# Prozessor.net
KiCad netlist of a schematic drawn in Altium Designer
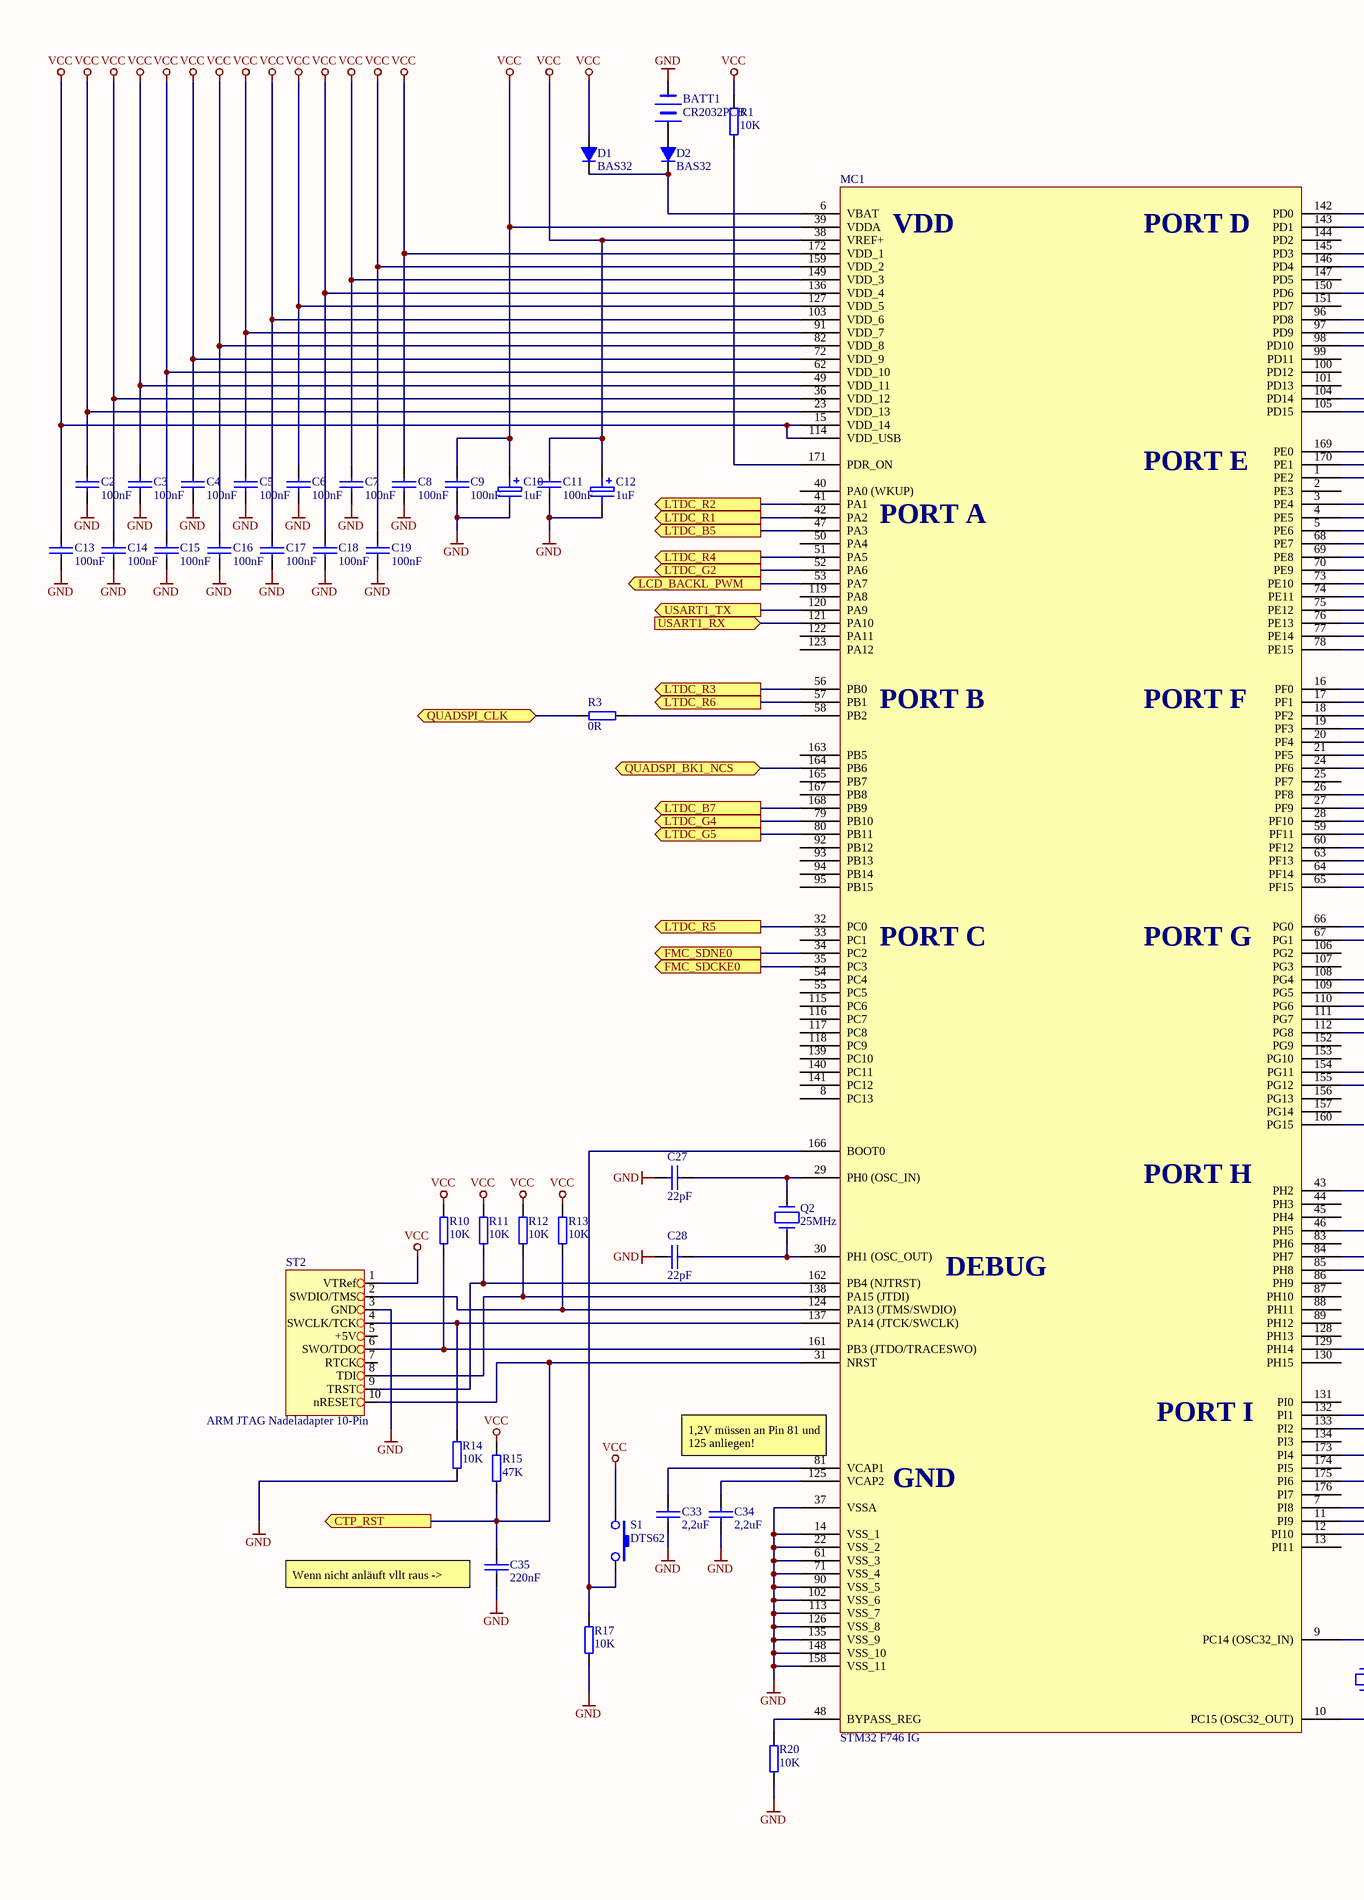
[diagram p0: Prozessor.SchDoc, left]
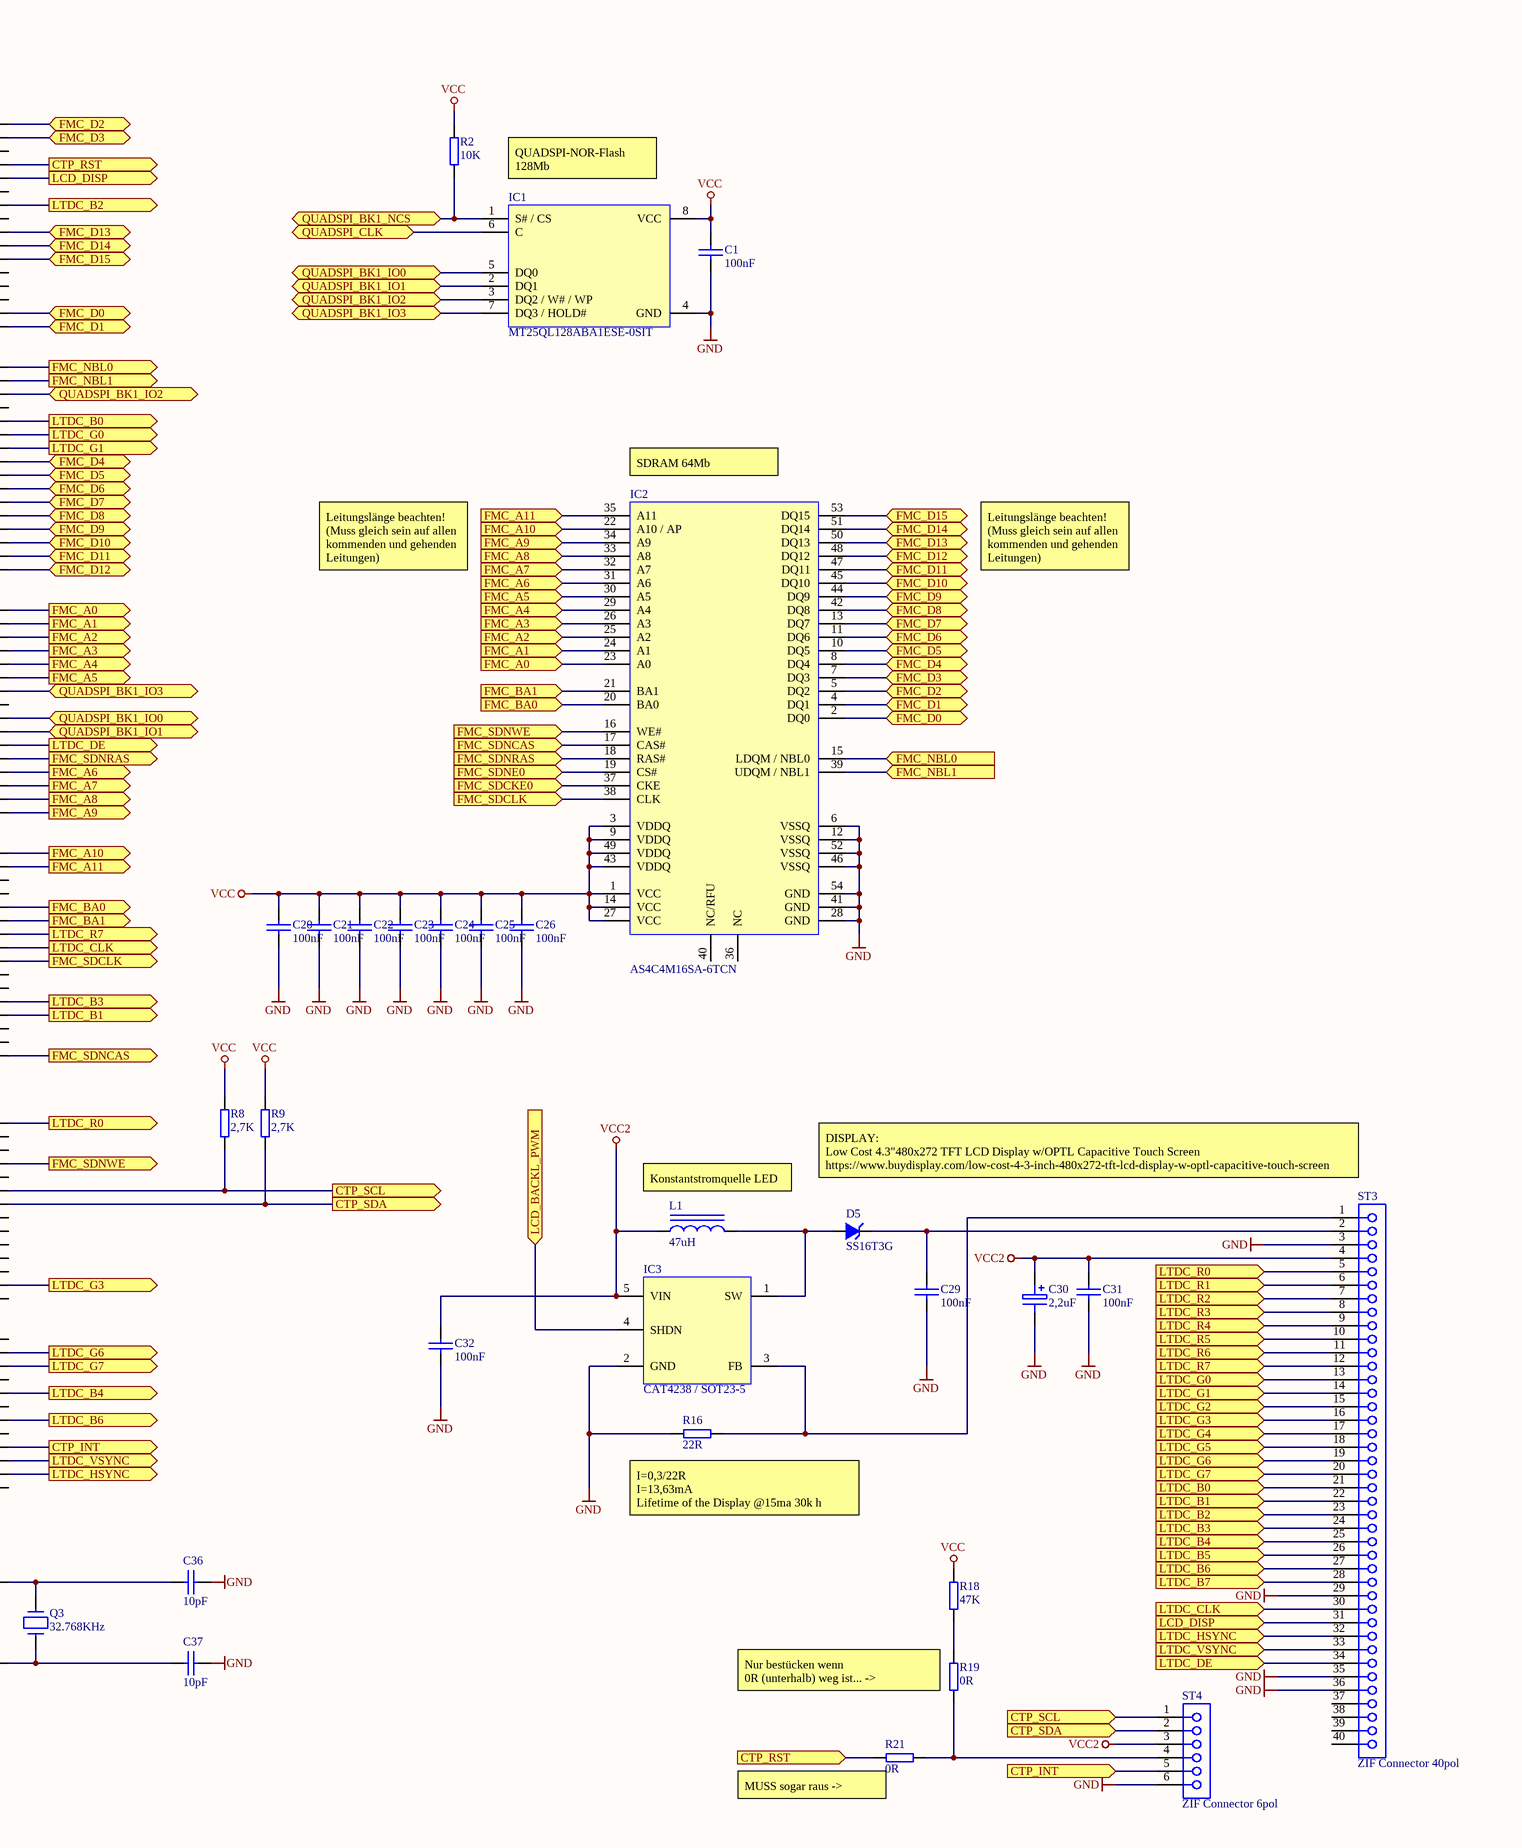
[diagram p1: Prozessor.SchDoc, right]

(export (version "E")
  (design (tool "Eeschema 10.0.6"))
  (components
    (comp (ref "BATT1")
      (value "CR2032PCB")
      (footprint "KnopfzellenhalterCR2032")
      (description "Knopfzellenhalter für Lithium-Batterie CR2032")
      (libsource (lib "Batterien") (part "CR2032 / HALTER"))
    )
    (comp (ref "C1")
      (value "100nF")
      (footprint "C0603")
      (description "100nF 0603 SMD-Keramik X7R 10% 50V")
      (libsource (lib "Kondensatoren") (part "0603 / 100nF"))
    )
    (comp (ref "C2")
      (value "100nF")
      (footprint "C0603")
      (description "100nF 0603 SMD-Keramik X7R 10% 50V")
      (libsource (lib "Kondensatoren") (part "0603 / 100nF"))
    )
    (comp (ref "C3")
      (value "100nF")
      (footprint "C0603")
      (description "100nF 0603 SMD-Keramik X7R 10% 50V")
      (libsource (lib "Kondensatoren") (part "0603 / 100nF"))
    )
    (comp (ref "C4")
      (value "100nF")
      (footprint "C0603")
      (description "100nF 0603 SMD-Keramik X7R 10% 50V")
      (libsource (lib "Kondensatoren") (part "0603 / 100nF"))
    )
    (comp (ref "C5")
      (value "100nF")
      (footprint "C0603")
      (description "100nF 0603 SMD-Keramik X7R 10% 50V")
      (libsource (lib "Kondensatoren") (part "0603 / 100nF"))
    )
    (comp (ref "C6")
      (value "100nF")
      (footprint "C0603")
      (description "100nF 0603 SMD-Keramik X7R 10% 50V")
      (libsource (lib "Kondensatoren") (part "0603 / 100nF"))
    )
    (comp (ref "C7")
      (value "100nF")
      (footprint "C0603")
      (description "100nF 0603 SMD-Keramik X7R 10% 50V")
      (libsource (lib "Kondensatoren") (part "0603 / 100nF"))
    )
    (comp (ref "C8")
      (value "100nF")
      (footprint "C0603")
      (description "100nF 0603 SMD-Keramik X7R 10% 50V")
      (libsource (lib "Kondensatoren") (part "0603 / 100nF"))
    )
    (comp (ref "C9")
      (value "100nF")
      (footprint "C0603")
      (description "100nF 0603 SMD-Keramik X7R 10% 50V")
      (libsource (lib "Kondensatoren") (part "0603 / 100nF"))
    )
    (comp (ref "C10")
      (value "1uF")
      (footprint "Alu-Elko4x5")
      (description "SMD-Alu Elko 1uF / 50V")
      (libsource (lib "Kondensatoren") (part "1uF / 50V"))
    )
    (comp (ref "C11")
      (value "100nF")
      (footprint "C0603")
      (description "100nF 0603 SMD-Keramik X7R 10% 50V")
      (libsource (lib "Kondensatoren") (part "0603 / 100nF"))
    )
    (comp (ref "C12")
      (value "1uF")
      (footprint "Alu-Elko4x5")
      (description "SMD-Alu Elko 1uF / 50V")
      (libsource (lib "Kondensatoren") (part "1uF / 50V"))
    )
    (comp (ref "C13")
      (value "100nF")
      (footprint "C0603")
      (description "100nF 0603 SMD-Keramik X7R 10% 50V")
      (libsource (lib "Kondensatoren") (part "0603 / 100nF"))
    )
    (comp (ref "C14")
      (value "100nF")
      (footprint "C0603")
      (description "100nF 0603 SMD-Keramik X7R 10% 50V")
      (libsource (lib "Kondensatoren") (part "0603 / 100nF"))
    )
    (comp (ref "C15")
      (value "100nF")
      (footprint "C0603")
      (description "100nF 0603 SMD-Keramik X7R 10% 50V")
      (libsource (lib "Kondensatoren") (part "0603 / 100nF"))
    )
    (comp (ref "C16")
      (value "100nF")
      (footprint "C0603")
      (description "100nF 0603 SMD-Keramik X7R 10% 50V")
      (libsource (lib "Kondensatoren") (part "0603 / 100nF"))
    )
    (comp (ref "C17")
      (value "100nF")
      (footprint "C0603")
      (description "100nF 0603 SMD-Keramik X7R 10% 50V")
      (libsource (lib "Kondensatoren") (part "0603 / 100nF"))
    )
    (comp (ref "C18")
      (value "100nF")
      (footprint "C0603")
      (description "100nF 0603 SMD-Keramik X7R 10% 50V")
      (libsource (lib "Kondensatoren") (part "0603 / 100nF"))
    )
    (comp (ref "C19")
      (value "100nF")
      (footprint "C0603")
      (description "100nF 0603 SMD-Keramik X7R 10% 50V")
      (libsource (lib "Kondensatoren") (part "0603 / 100nF"))
    )
    (comp (ref "C20")
      (value "100nF")
      (footprint "C0603")
      (description "100nF 0603 SMD-Keramik X7R 10% 50V")
      (libsource (lib "Kondensatoren") (part "0603 / 100nF"))
    )
    (comp (ref "C21")
      (value "100nF")
      (footprint "C0603")
      (description "100nF 0603 SMD-Keramik X7R 10% 50V")
      (libsource (lib "Kondensatoren") (part "0603 / 100nF"))
    )
    (comp (ref "C22")
      (value "100nF")
      (footprint "C0603")
      (description "100nF 0603 SMD-Keramik X7R 10% 50V")
      (libsource (lib "Kondensatoren") (part "0603 / 100nF"))
    )
    (comp (ref "C23")
      (value "100nF")
      (footprint "C0603")
      (description "100nF 0603 SMD-Keramik X7R 10% 50V")
      (libsource (lib "Kondensatoren") (part "0603 / 100nF"))
    )
    (comp (ref "C24")
      (value "100nF")
      (footprint "C0603")
      (description "100nF 0603 SMD-Keramik X7R 10% 50V")
      (libsource (lib "Kondensatoren") (part "0603 / 100nF"))
    )
    (comp (ref "C25")
      (value "100nF")
      (footprint "C0603")
      (description "100nF 0603 SMD-Keramik X7R 10% 50V")
      (libsource (lib "Kondensatoren") (part "0603 / 100nF"))
    )
    (comp (ref "C26")
      (value "100nF")
      (footprint "C0603")
      (description "100nF 0603 SMD-Keramik X7R 10% 50V")
      (libsource (lib "Kondensatoren") (part "0603 / 100nF"))
    )
    (comp (ref "C27")
      (value "22pF")
      (footprint "C0603")
      (description "22pF 0603 SMD-Keramik X7R 10% 50V")
      (libsource (lib "Kondensatoren") (part "0603 / 22pF"))
    )
    (comp (ref "C28")
      (value "22pF")
      (footprint "C0603")
      (description "22pF 0603 SMD-Keramik X7R 10% 50V")
      (libsource (lib "Kondensatoren") (part "0603 / 22pF"))
    )
    (comp (ref "C29")
      (value "100nF")
      (footprint "C0603")
      (description "100nF 0603 SMD-Keramik X7R 10% 50V")
      (libsource (lib "Kondensatoren") (part "0603 / 100nF"))
    )
    (comp (ref "C30")
      (value "2,2uF")
      (footprint "CB")
      (description "SMD-Tantal 2,2uF / 25V 20% B")
      (libsource (lib "Kondensatoren") (part "2,2uF / 25V"))
    )
    (comp (ref "C31")
      (value "100nF")
      (footprint "C0603")
      (description "100nF 0603 SMD-Keramik X7R 10% 50V")
      (libsource (lib "Kondensatoren") (part "0603 / 100nF"))
    )
    (comp (ref "C32")
      (value "100nF")
      (footprint "C0603")
      (description "100nF 0603 SMD-Keramik X7R 10% 50V")
      (libsource (lib "Kondensatoren") (part "0603 / 100nF"))
    )
    (comp (ref "C33")
      (value "2,2uF")
      (footprint "C1206")
      (description "2,2uF 1206 SMD-Keramik 10% 50V XR7")
      (libsource (lib "Kondensatoren") (part "1206 / 2,2uF"))
    )
    (comp (ref "C34")
      (value "2,2uF")
      (footprint "C1206")
      (description "2,2uF 1206 SMD-Keramik 10% 50V XR7")
      (libsource (lib "Kondensatoren") (part "1206 / 2,2uF"))
    )
    (comp (ref "C35")
      (value "220nF")
      (footprint "C0603")
      (description "220nF 0603 SMD-Keramik X7R 10% 50V")
      (libsource (lib "Kondensatoren") (part "0603 / 220nF"))
    )
    (comp (ref "C36")
      (value "10pF")
      (footprint "C0603")
      (description "10pF 0603 SMD-Keramik X7R 10% 50V")
      (libsource (lib "Kondensatoren") (part "0603 / 10pF"))
    )
    (comp (ref "C37")
      (value "10pF")
      (footprint "C0603")
      (description "10pF 0603 SMD-Keramik X7R 10% 50V")
      (libsource (lib "Kondensatoren") (part "0603 / 10pF"))
    )
    (comp (ref "D1")
      (value "BAS32")
      (footprint "Minimelf")
      (description "SMD Si-Diode 100V 0,2A Minimelf")
      (libsource (lib "Dioden") (part "BAS32 / MINIMELF"))
    )
    (comp (ref "D2")
      (value "BAS32")
      (footprint "Minimelf")
      (description "SMD Si-Diode 100V 0,2A Minimelf")
      (libsource (lib "Dioden") (part "BAS32 / MINIMELF"))
    )
    (comp (ref "D5")
      (value "SS16T3G")
      (footprint "DO214AC/SMA")
      (description "Schottky Diode 60V 1A")
      (libsource (lib "Dioden") (part "SS16T3G"))
    )
    (comp (ref "IC1")
      (value "MT25QL128ABA1ESE-0SIT")
      (footprint "SOP2-8-208 (SO8W)")
      (description "SPI-NOR-Flash 128Mb")
      (libsource (lib "Speicher") (part "MT25QL128ABA1ESE-0SIT / SO8W"))
    )
    (comp (ref "IC2")
      (value "AS4C4M16SA-6TCN")
      (footprint "TSSOP(2)54")
      (description "SDRAM 64Mb")
      (libsource (lib "Speicher") (part "AS4C4M16SA-6TCN / SO8W_1"))
    )
    (comp (ref "IC3")
      (value "CAT4238 / SOT23-5")
      (footprint "SOT23-5")
      (description "LED Driver, Boost, 10LED")
      (libsource (lib "Linear") (part "CAT4238 / SOT23-5"))
    )
    (comp (ref "L1")
      (value "47uH")
      (footprint "P8X9")
      (description "Tonneninduktivität stehend")
      (libsource (lib "Induktivitaeten") (part "47uH / P8X9"))
    )
    (comp (ref "MC1")
      (value "STM32 F746 IG")
      (footprint "QFP24x24-176-05")
      (description "LQFP 1176 24x24")
      (libsource (lib "Microcontroller") (part "STM32 F746 IG"))
    )
    (comp (ref "Q2")
      (value "25MHz")
      (footprint "HC49S4SMD")
      (description "SMD Schwingquarz 8MHz HC49S$SMD 30ppm")
      (libsource (lib "Quarze") (part "HC49 S / 8"))
    )
    (comp (ref "Q3")
      (value "32.768KHz")
      (footprint "SMD Uhrenquarz klein")
      (description "SMD Schwingquarz 32.768KHz 15ppm")
      (libsource (lib "Quarze") (part "ZM315-32.768"))
    )
    (comp (ref "R1")
      (value "10K")
      (footprint "R0603")
      (description "10K 0603 SMD-Kohleschicht 1% 0,1W")
      (libsource (lib "Widerstaende") (part "0603 / 10K"))
    )
    (comp (ref "R2")
      (value "10K")
      (footprint "R0603")
      (description "10K 0603 SMD-Kohleschicht 1% 0,1W")
      (libsource (lib "Widerstaende") (part "0603 / 10K"))
    )
    (comp (ref "R3")
      (value "0R")
      (footprint "R0603")
      (description "0R 0603 SMD-Kohleschicht 1% 0,1W")
      (libsource (lib "Widerstaende") (part "0603 / 0R"))
    )
    (comp (ref "R8")
      (value "2,7K")
      (footprint "R0603")
      (description "2,7K 0603 SMD-Kohleschicht 1% 0,1W")
      (libsource (lib "Widerstaende") (part "0603 / 2,7K"))
    )
    (comp (ref "R9")
      (value "2,7K")
      (footprint "R0603")
      (description "2,7K 0603 SMD-Kohleschicht 1% 0,1W")
      (libsource (lib "Widerstaende") (part "0603 / 2,7K"))
    )
    (comp (ref "R10")
      (value "10K")
      (footprint "R0603")
      (description "10K 0603 SMD-Kohleschicht 1% 0,1W")
      (libsource (lib "Widerstaende") (part "0603 / 10K"))
    )
    (comp (ref "R11")
      (value "10K")
      (footprint "R0603")
      (description "10K 0603 SMD-Kohleschicht 1% 0,1W")
      (libsource (lib "Widerstaende") (part "0603 / 10K"))
    )
    (comp (ref "R12")
      (value "10K")
      (footprint "R0603")
      (description "10K 0603 SMD-Kohleschicht 1% 0,1W")
      (libsource (lib "Widerstaende") (part "0603 / 10K"))
    )
    (comp (ref "R13")
      (value "10K")
      (footprint "R0603")
      (description "10K 0603 SMD-Kohleschicht 1% 0,1W")
      (libsource (lib "Widerstaende") (part "0603 / 10K"))
    )
    (comp (ref "R14")
      (value "10K")
      (footprint "R0603")
      (description "10K 0603 SMD-Kohleschicht 1% 0,1W")
      (libsource (lib "Widerstaende") (part "0603 / 10K"))
    )
    (comp (ref "R15")
      (value "47K")
      (footprint "R0603")
      (description "47K 0603 SMD-Kohleschicht 1% 0,1W")
      (libsource (lib "Widerstaende") (part "0603 / 47K"))
    )
    (comp (ref "R16")
      (value "22R")
      (footprint "R0603")
      (description "22R 0603 SMD-Kohleschicht 1% 0,1W")
      (libsource (lib "Widerstaende") (part "0603 / 22R"))
    )
    (comp (ref "R17")
      (value "10K")
      (footprint "R0603")
      (description "10K 0603 SMD-Kohleschicht 1% 0,1W")
      (libsource (lib "Widerstaende") (part "0603 / 10K"))
    )
    (comp (ref "R18")
      (value "47K")
      (footprint "R0603")
      (description "47K 0603 SMD-Kohleschicht 1% 0,1W")
      (libsource (lib "Widerstaende") (part "0603 / 47K"))
    )
    (comp (ref "R19")
      (value "0R")
      (footprint "R0603")
      (description "0R 0603 SMD-Kohleschicht 1% 0,1W")
      (libsource (lib "Widerstaende") (part "0603 / 0R"))
    )
    (comp (ref "R20")
      (value "10K")
      (footprint "R0603")
      (description "10K 0603 SMD-Kohleschicht 1% 0,1W")
      (libsource (lib "Widerstaende") (part "0603 / 10K"))
    )
    (comp (ref "R21")
      (value "0R")
      (footprint "R0603")
      (description "0R 0603 SMD-Kohleschicht 1% 0,1W")
      (libsource (lib "Widerstaende") (part "0603 / 0R"))
    )
    (comp (ref "S1")
      (value "DTS62")
      (footprint "DTS62")
      (description "Leiterplattentaster 6x6mm 1,6N")
      (libsource (lib "Schalter") (part "DTS62 / N"))
    )
    (comp (ref "ST2")
      (value "ARM JTAG Nadeladapter 10-Pin")
      (footprint "NADELADAPTER-10")
      (libsource (lib "Steckverbinder") (part "ARM JTAG Nadeladapter 10-Pin"))
    )
    (comp (ref "ST3")
      (value "ZIF Connector 40pol")
      (footprint "ZIF Connector 40pol")
      (description "ZIF Connector 40pol Top Contact")
      (libsource (lib "Steckverbinder") (part "ZIF Connector 40pol Top Contact"))
    )
    (comp (ref "ST4")
      (value "ZIF Connector 6pol")
      (footprint "ZIF Connector 6pol")
      (description "ZIF Connector 6pol Top Contact")
      (libsource (lib "Steckverbinder") (part "ZIF Connector 6pol Top Contact"))
    )
  )
  (nets
    (net (code "1") (name "/CTP_INT") (class "Default")
      (node (ref "MC1") (pin "7") (pinfunction "PI8_7") (pintype "passive"))
      (node (ref "ST4") (pin "5") (pinfunction "5_5") (pintype "passive"))
    )
    (net (code "2") (name "/CTP_RST") (class "Default")
      (node (ref "C35") (pin "2") (pintype "passive"))
      (node (ref "MC1") (pin "145") (pinfunction "PD3_145") (pintype "passive"))
      (node (ref "MC1") (pin "31") (pinfunction "NRST_31") (pintype "passive"))
      (node (ref "R15") (pin "1") (pintype "passive"))
      (node (ref "R21") (pin "1") (pintype "passive"))
      (node (ref "ST2") (pin "10") (pinfunction "nRESET_10") (pintype "passive"))
    )
    (net (code "3") (name "/CTP_SCL") (class "Default")
      (node (ref "MC1") (pin "84") (pinfunction "PH7_84") (pintype "passive"))
      (node (ref "R8") (pin "1") (pintype "passive"))
      (node (ref "ST4") (pin "1") (pinfunction "1_1") (pintype "passive"))
    )
    (net (code "4") (name "/CTP_SDA") (class "Default")
      (node (ref "MC1") (pin "85") (pinfunction "PH8_85") (pintype "passive"))
      (node (ref "R9") (pin "1") (pintype "passive"))
      (node (ref "ST4") (pin "2") (pinfunction "2_2") (pintype "passive"))
    )
    (net (code "5") (name "/FMC_A0") (class "Default")
      (node (ref "IC2") (pin "23") (pinfunction "A0_23") (pintype "passive"))
      (node (ref "MC1") (pin "16") (pinfunction "PF0_16") (pintype "passive"))
    )
    (net (code "6") (name "/FMC_A1") (class "Default")
      (node (ref "IC2") (pin "24") (pinfunction "A1_24") (pintype "passive"))
      (node (ref "MC1") (pin "17") (pinfunction "PF1_17") (pintype "passive"))
    )
    (net (code "7") (name "/FMC_A2") (class "Default")
      (node (ref "IC2") (pin "25") (pinfunction "A2_25") (pintype "passive"))
      (node (ref "MC1") (pin "18") (pinfunction "PF2_18") (pintype "passive"))
    )
    (net (code "8") (name "/FMC_A3") (class "Default")
      (node (ref "IC2") (pin "26") (pinfunction "A3_26") (pintype "passive"))
      (node (ref "MC1") (pin "19") (pinfunction "PF3_19") (pintype "passive"))
    )
    (net (code "9") (name "/FMC_A4") (class "Default")
      (node (ref "IC2") (pin "29") (pinfunction "A4_29") (pintype "passive"))
      (node (ref "MC1") (pin "20") (pinfunction "PF4_20") (pintype "passive"))
    )
    (net (code "10") (name "/FMC_A5") (class "Default")
      (node (ref "IC2") (pin "30") (pinfunction "A5_30") (pintype "passive"))
      (node (ref "MC1") (pin "21") (pinfunction "PF5_21") (pintype "passive"))
    )
    (net (code "11") (name "/FMC_A6") (class "Default")
      (node (ref "IC2") (pin "31") (pinfunction "A6_31") (pintype "passive"))
      (node (ref "MC1") (pin "60") (pinfunction "PF12_60") (pintype "passive"))
    )
    (net (code "12") (name "/FMC_A7") (class "Default")
      (node (ref "IC2") (pin "32") (pinfunction "A7_32") (pintype "passive"))
      (node (ref "MC1") (pin "63") (pinfunction "PF13_63") (pintype "passive"))
    )
    (net (code "13") (name "/FMC_A8") (class "Default")
      (node (ref "IC2") (pin "33") (pinfunction "A8_33") (pintype "passive"))
      (node (ref "MC1") (pin "64") (pinfunction "PF14_64") (pintype "passive"))
    )
    (net (code "14") (name "/FMC_A9") (class "Default")
      (node (ref "IC2") (pin "34") (pinfunction "A9_34") (pintype "passive"))
      (node (ref "MC1") (pin "65") (pinfunction "PF15_65") (pintype "passive"))
    )
    (net (code "15") (name "/FMC_A10") (class "Default")
      (node (ref "IC2") (pin "22") (pinfunction "A10_/_AP_22") (pintype "passive"))
      (node (ref "MC1") (pin "66") (pinfunction "PG0_66") (pintype "passive"))
    )
    (net (code "16") (name "/FMC_A11") (class "Default")
      (node (ref "IC2") (pin "35") (pinfunction "A11_35") (pintype "passive"))
      (node (ref "MC1") (pin "67") (pinfunction "PG1_67") (pintype "passive"))
    )
    (net (code "17") (name "/FMC_BA0") (class "Default")
      (node (ref "IC2") (pin "20") (pinfunction "BA0_20") (pintype "passive"))
      (node (ref "MC1") (pin "108") (pinfunction "PG4_108") (pintype "passive"))
    )
    (net (code "18") (name "/FMC_BA1") (class "Default")
      (node (ref "IC2") (pin "21") (pinfunction "BA1_21") (pintype "passive"))
      (node (ref "MC1") (pin "109") (pinfunction "PG5_109") (pintype "passive"))
    )
    (net (code "19") (name "/FMC_D0") (class "Default")
      (node (ref "IC2") (pin "2") (pinfunction "DQ0_2") (pintype "passive"))
      (node (ref "MC1") (pin "104") (pinfunction "PD14_104") (pintype "passive"))
    )
    (net (code "20") (name "/FMC_D1") (class "Default")
      (node (ref "IC2") (pin "4") (pinfunction "DQ1_4") (pintype "passive"))
      (node (ref "MC1") (pin "105") (pinfunction "PD15_105") (pintype "passive"))
    )
    (net (code "21") (name "/FMC_D2") (class "Default")
      (node (ref "IC2") (pin "5") (pinfunction "DQ2_5") (pintype "passive"))
      (node (ref "MC1") (pin "142") (pinfunction "PD0_142") (pintype "passive"))
    )
    (net (code "22") (name "/FMC_D3") (class "Default")
      (node (ref "IC2") (pin "7") (pinfunction "DQ3_7") (pintype "passive"))
      (node (ref "MC1") (pin "143") (pinfunction "PD1_143") (pintype "passive"))
    )
    (net (code "23") (name "/FMC_D4") (class "Default")
      (node (ref "IC2") (pin "8") (pinfunction "DQ4_8") (pintype "passive"))
      (node (ref "MC1") (pin "68") (pinfunction "PE7_68") (pintype "passive"))
    )
    (net (code "24") (name "/FMC_D5") (class "Default")
      (node (ref "IC2") (pin "10") (pinfunction "DQ5_10") (pintype "passive"))
      (node (ref "MC1") (pin "69") (pinfunction "PE8_69") (pintype "passive"))
    )
    (net (code "25") (name "/FMC_D6") (class "Default")
      (node (ref "IC2") (pin "11") (pinfunction "DQ6_11") (pintype "passive"))
      (node (ref "MC1") (pin "70") (pinfunction "PE9_70") (pintype "passive"))
    )
    (net (code "26") (name "/FMC_D7") (class "Default")
      (node (ref "IC2") (pin "13") (pinfunction "DQ7_13") (pintype "passive"))
      (node (ref "MC1") (pin "73") (pinfunction "PE10_73") (pintype "passive"))
    )
    (net (code "27") (name "/FMC_D8") (class "Default")
      (node (ref "IC2") (pin "42") (pinfunction "DQ8_42") (pintype "passive"))
      (node (ref "MC1") (pin "74") (pinfunction "PE11_74") (pintype "passive"))
    )
    (net (code "28") (name "/FMC_D9") (class "Default")
      (node (ref "IC2") (pin "44") (pinfunction "DQ9_44") (pintype "passive"))
      (node (ref "MC1") (pin "75") (pinfunction "PE12_75") (pintype "passive"))
    )
    (net (code "29") (name "/FMC_D10") (class "Default")
      (node (ref "IC2") (pin "45") (pinfunction "DQ10_45") (pintype "passive"))
      (node (ref "MC1") (pin "76") (pinfunction "PE13_76") (pintype "passive"))
    )
    (net (code "30") (name "/FMC_D11") (class "Default")
      (node (ref "IC2") (pin "47") (pinfunction "DQ11_47") (pintype "passive"))
      (node (ref "MC1") (pin "77") (pinfunction "PE14_77") (pintype "passive"))
    )
    (net (code "31") (name "/FMC_D12") (class "Default")
      (node (ref "IC2") (pin "48") (pinfunction "DQ12_48") (pintype "passive"))
      (node (ref "MC1") (pin "78") (pinfunction "PE15_78") (pintype "passive"))
    )
    (net (code "32") (name "/FMC_D13") (class "Default")
      (node (ref "IC2") (pin "50") (pinfunction "DQ13_50") (pintype "passive"))
      (node (ref "MC1") (pin "96") (pinfunction "PD8_96") (pintype "passive"))
    )
    (net (code "33") (name "/FMC_D14") (class "Default")
      (node (ref "IC2") (pin "51") (pinfunction "DQ14_51") (pintype "passive"))
      (node (ref "MC1") (pin "97") (pinfunction "PD9_97") (pintype "passive"))
    )
    (net (code "34") (name "/FMC_D15") (class "Default")
      (node (ref "IC2") (pin "53") (pinfunction "DQ15_53") (pintype "passive"))
      (node (ref "MC1") (pin "98") (pinfunction "PD10_98") (pintype "passive"))
    )
    (net (code "35") (name "/FMC_NBL0") (class "Default")
      (node (ref "IC2") (pin "15") (pinfunction "LDQM_/_NBL0_15") (pintype "passive"))
      (node (ref "MC1") (pin "169") (pinfunction "PE0_169") (pintype "passive"))
    )
    (net (code "36") (name "/FMC_NBL1") (class "Default")
      (node (ref "IC2") (pin "39") (pinfunction "UDQM_/_NBL1_39") (pintype "passive"))
      (node (ref "MC1") (pin "170") (pinfunction "PE1_170") (pintype "passive"))
    )
    (net (code "37") (name "/FMC_SDCKE0") (class "Default")
      (node (ref "IC2") (pin "37") (pinfunction "CKE_37") (pintype "passive"))
      (node (ref "MC1") (pin "35") (pinfunction "PC3_35") (pintype "passive"))
    )
    (net (code "38") (name "/FMC_SDCLK") (class "Default")
      (node (ref "IC2") (pin "38") (pinfunction "CLK_38") (pintype "passive"))
      (node (ref "MC1") (pin "112") (pinfunction "PG8_112") (pintype "passive"))
    )
    (net (code "39") (name "/FMC_SDNCAS") (class "Default")
      (node (ref "IC2") (pin "17") (pinfunction "CAS#_17") (pintype "passive"))
      (node (ref "MC1") (pin "160") (pinfunction "PG15_160") (pintype "passive"))
    )
    (net (code "40") (name "/FMC_SDNE0") (class "Default")
      (node (ref "IC2") (pin "19") (pinfunction "CS#_19") (pintype "passive"))
      (node (ref "MC1") (pin "34") (pinfunction "PC2_34") (pintype "passive"))
    )
    (net (code "41") (name "/FMC_SDNRAS") (class "Default")
      (node (ref "IC2") (pin "18") (pinfunction "RAS#_18") (pintype "passive"))
      (node (ref "MC1") (pin "59") (pinfunction "PF11_59") (pintype "passive"))
    )
    (net (code "42") (name "/FMC_SDNWE") (class "Default")
      (node (ref "IC2") (pin "16") (pinfunction "WE#_16") (pintype "passive"))
      (node (ref "MC1") (pin "46") (pinfunction "PH5_46") (pintype "passive"))
    )
    (net (code "43") (name "/LCD_BACKL_PWM") (class "Default")
      (node (ref "IC3") (pin "4") (pinfunction "SHDN_4") (pintype "passive"))
      (node (ref "MC1") (pin "53") (pinfunction "PA7_53") (pintype "passive"))
    )
    (net (code "44") (name "/LCD_DISP") (class "Default")
      (node (ref "MC1") (pin "146") (pinfunction "PD4_146") (pintype "passive"))
      (node (ref "ST3") (pin "31") (pinfunction "31_31") (pintype "passive"))
    )
    (net (code "45") (name "/LTDC_B0") (class "Default")
      (node (ref "MC1") (pin "3") (pinfunction "PE4_3") (pintype "passive"))
      (node (ref "ST3") (pin "21") (pinfunction "21_21") (pintype "passive"))
    )
    (net (code "46") (name "/LTDC_B1") (class "Default")
      (node (ref "MC1") (pin "155") (pinfunction "PG12_155") (pintype "passive"))
      (node (ref "ST3") (pin "22") (pinfunction "22_22") (pintype "passive"))
    )
    (net (code "47") (name "/LTDC_B2") (class "Default")
      (node (ref "MC1") (pin "150") (pinfunction "PD6_150") (pintype "passive"))
      (node (ref "ST3") (pin "23") (pinfunction "23_23") (pintype "passive"))
    )
    (net (code "48") (name "/LTDC_B3") (class "Default")
      (node (ref "MC1") (pin "154") (pinfunction "PG11_154") (pintype "passive"))
      (node (ref "ST3") (pin "24") (pinfunction "24_24") (pintype "passive"))
    )
    (net (code "49") (name "/LTDC_B4") (class "Default")
      (node (ref "MC1") (pin "173") (pinfunction "PI4_173") (pintype "passive"))
      (node (ref "ST3") (pin "25") (pinfunction "25_25") (pintype "passive"))
    )
    (net (code "50") (name "/LTDC_B5") (class "Default")
      (node (ref "MC1") (pin "47") (pinfunction "PA3_47") (pintype "passive"))
      (node (ref "ST3") (pin "26") (pinfunction "26_26") (pintype "passive"))
    )
    (net (code "51") (name "/LTDC_B6") (class "Default")
      (node (ref "MC1") (pin "175") (pinfunction "PI6_175") (pintype "passive"))
      (node (ref "ST3") (pin "27") (pinfunction "27_27") (pintype "passive"))
    )
    (net (code "52") (name "/LTDC_B7") (class "Default")
      (node (ref "MC1") (pin "168") (pinfunction "PB9_168") (pintype "passive"))
      (node (ref "ST3") (pin "28") (pinfunction "28_28") (pintype "passive"))
    )
    (net (code "53") (name "/LTDC_CLK") (class "Default")
      (node (ref "MC1") (pin "111") (pinfunction "PG7_111") (pintype "passive"))
      (node (ref "ST3") (pin "30") (pinfunction "30_30") (pintype "passive"))
    )
    (net (code "54") (name "/LTDC_DE") (class "Default")
      (node (ref "MC1") (pin "28") (pinfunction "PF10_28") (pintype "passive"))
      (node (ref "ST3") (pin "34") (pinfunction "34_34") (pintype "passive"))
    )
    (net (code "55") (name "/LTDC_G0") (class "Default")
      (node (ref "MC1") (pin "4") (pinfunction "PE5_4") (pintype "passive"))
      (node (ref "ST3") (pin "13") (pinfunction "13_13") (pintype "passive"))
    )
    (net (code "56") (name "/LTDC_G1") (class "Default")
      (node (ref "MC1") (pin "5") (pinfunction "PE6_5") (pintype "passive"))
      (node (ref "ST3") (pin "14") (pinfunction "14_14") (pintype "passive"))
    )
    (net (code "57") (name "/LTDC_G2") (class "Default")
      (node (ref "MC1") (pin "52") (pinfunction "PA6_52") (pintype "passive"))
      (node (ref "ST3") (pin "15") (pinfunction "15_15") (pintype "passive"))
    )
    (net (code "58") (name "/LTDC_G3") (class "Default")
      (node (ref "MC1") (pin "129") (pinfunction "PH14_129") (pintype "passive"))
      (node (ref "ST3") (pin "16") (pinfunction "16_16") (pintype "passive"))
    )
    (net (code "59") (name "/LTDC_G4") (class "Default")
      (node (ref "MC1") (pin "79") (pinfunction "PB10_79") (pintype "passive"))
      (node (ref "ST3") (pin "17") (pinfunction "17_17") (pintype "passive"))
    )
    (net (code "60") (name "/LTDC_G5") (class "Default")
      (node (ref "MC1") (pin "80") (pinfunction "PB11_80") (pintype "passive"))
      (node (ref "ST3") (pin "18") (pinfunction "18_18") (pintype "passive"))
    )
    (net (code "61") (name "/LTDC_G6") (class "Default")
      (node (ref "MC1") (pin "132") (pinfunction "PI1_132") (pintype "passive"))
      (node (ref "ST3") (pin "19") (pinfunction "19_19") (pintype "passive"))
    )
    (net (code "62") (name "/LTDC_G7") (class "Default")
      (node (ref "MC1") (pin "133") (pinfunction "PI2_133") (pintype "passive"))
      (node (ref "ST3") (pin "20") (pinfunction "20_20") (pintype "passive"))
    )
    (net (code "63") (name "/LTDC_HSYNC") (class "Default")
      (node (ref "MC1") (pin "12") (pinfunction "PI10_12") (pintype "passive"))
      (node (ref "ST3") (pin "32") (pinfunction "32_32") (pintype "passive"))
    )
    (net (code "64") (name "/LTDC_R0") (class "Default")
      (node (ref "MC1") (pin "43") (pinfunction "PH2_43") (pintype "passive"))
      (node (ref "ST3") (pin "5") (pinfunction "5_5") (pintype "passive"))
    )
    (net (code "65") (name "/LTDC_R1") (class "Default")
      (node (ref "MC1") (pin "42") (pinfunction "PA2_42") (pintype "passive"))
      (node (ref "ST3") (pin "6") (pinfunction "6_6") (pintype "passive"))
    )
    (net (code "66") (name "/LTDC_R2") (class "Default")
      (node (ref "MC1") (pin "41") (pinfunction "PA1_41") (pintype "passive"))
      (node (ref "ST3") (pin "7") (pinfunction "7_7") (pintype "passive"))
    )
    (net (code "67") (name "/LTDC_R3") (class "Default")
      (node (ref "MC1") (pin "56") (pinfunction "PB0_56") (pintype "passive"))
      (node (ref "ST3") (pin "8") (pinfunction "8_8") (pintype "passive"))
    )
    (net (code "68") (name "/LTDC_R4") (class "Default")
      (node (ref "MC1") (pin "51") (pinfunction "PA5_51") (pintype "passive"))
      (node (ref "ST3") (pin "9") (pinfunction "9_9") (pintype "passive"))
    )
    (net (code "69") (name "/LTDC_R5") (class "Default")
      (node (ref "MC1") (pin "32") (pinfunction "PC0_32") (pintype "passive"))
      (node (ref "ST3") (pin "10") (pinfunction "10_10") (pintype "passive"))
    )
    (net (code "70") (name "/LTDC_R6") (class "Default")
      (node (ref "MC1") (pin "57") (pinfunction "PB1_57") (pintype "passive"))
      (node (ref "ST3") (pin "11") (pinfunction "11_11") (pintype "passive"))
    )
    (net (code "71") (name "/LTDC_R7") (class "Default")
      (node (ref "MC1") (pin "110") (pinfunction "PG6_110") (pintype "passive"))
      (node (ref "ST3") (pin "12") (pinfunction "12_12") (pintype "passive"))
    )
    (net (code "72") (name "/LTDC_VSYNC") (class "Default")
      (node (ref "MC1") (pin "11") (pinfunction "PI9_11") (pintype "passive"))
      (node (ref "ST3") (pin "33") (pinfunction "33_33") (pintype "passive"))
    )
    (net (code "73") (name "/QUADSPI_BK1_IO0") (class "Default")
      (node (ref "IC1") (pin "5") (pinfunction "DQ0_5") (pintype "passive"))
      (node (ref "MC1") (pin "26") (pinfunction "PF8_26") (pintype "passive"))
    )
    (net (code "74") (name "/QUADSPI_BK1_IO1") (class "Default")
      (node (ref "IC1") (pin "2") (pinfunction "DQ1_2") (pintype "passive"))
      (node (ref "MC1") (pin "27") (pinfunction "PF9_27") (pintype "passive"))
    )
    (net (code "75") (name "/QUADSPI_BK1_IO2") (class "Default")
      (node (ref "IC1") (pin "3") (pinfunction "DQ2_/_W#_/_WP_3") (pintype "passive"))
      (node (ref "MC1") (pin "1") (pinfunction "PE2_1") (pintype "passive"))
    )
    (net (code "76") (name "/QUADSPI_BK1_IO3") (class "Default")
      (node (ref "IC1") (pin "7") (pinfunction "DQ3_/_HOLD#_7") (pintype "passive"))
      (node (ref "MC1") (pin "24") (pinfunction "PF6_24") (pintype "passive"))
    )
    (net (code "77") (name "/QUADSPI_BK1_NCS") (class "Default")
      (node (ref "IC1") (pin "1") (pinfunction "S#_/_CS_1") (pintype "passive"))
      (node (ref "MC1") (pin "164") (pinfunction "PB6_164") (pintype "passive"))
      (node (ref "R2") (pin "1") (pintype "passive"))
    )
    (net (code "78") (name "/QUADSPI_CLK") (class "Default")
      (node (ref "IC1") (pin "6") (pinfunction "C_6") (pintype "passive"))
      (node (ref "R3") (pin "1") (pintype "passive"))
    )
    (net (code "79") (name "/USART1_RX") (class "Default")
      (node (ref "MC1") (pin "121") (pinfunction "PA10_121") (pintype "passive"))
    )
    (net (code "80") (name "/USART1_TX") (class "Default")
      (node (ref "MC1") (pin "120") (pinfunction "PA9_120") (pintype "passive"))
    )
    (net (code "81") (name "GND") (class "Default")
      (node (ref "BATT1") (pin "1") (pinfunction "-_1") (pintype "passive"))
      (node (ref "C1") (pin "1") (pintype "passive"))
      (node (ref "C10") (pin "2") (pintype "passive"))
      (node (ref "C11") (pin "1") (pintype "passive"))
      (node (ref "C12") (pin "2") (pintype "passive"))
      (node (ref "C13") (pin "1") (pintype "passive"))
      (node (ref "C14") (pin "1") (pintype "passive"))
      (node (ref "C15") (pin "1") (pintype "passive"))
      (node (ref "C16") (pin "1") (pintype "passive"))
      (node (ref "C17") (pin "1") (pintype "passive"))
      (node (ref "C18") (pin "1") (pintype "passive"))
      (node (ref "C19") (pin "1") (pintype "passive"))
      (node (ref "C2") (pin "1") (pintype "passive"))
      (node (ref "C20") (pin "1") (pintype "passive"))
      (node (ref "C21") (pin "1") (pintype "passive"))
      (node (ref "C22") (pin "1") (pintype "passive"))
      (node (ref "C23") (pin "1") (pintype "passive"))
      (node (ref "C24") (pin "1") (pintype "passive"))
      (node (ref "C25") (pin "1") (pintype "passive"))
      (node (ref "C26") (pin "1") (pintype "passive"))
      (node (ref "C27") (pin "1") (pintype "passive"))
      (node (ref "C28") (pin "1") (pintype "passive"))
      (node (ref "C29") (pin "1") (pintype "passive"))
      (node (ref "C3") (pin "1") (pintype "passive"))
      (node (ref "C30") (pin "1") (pinfunction "K_1") (pintype "passive"))
      (node (ref "C31") (pin "1") (pintype "passive"))
      (node (ref "C32") (pin "1") (pintype "passive"))
      (node (ref "C33") (pin "2") (pintype "passive"))
      (node (ref "C34") (pin "2") (pintype "passive"))
      (node (ref "C35") (pin "1") (pintype "passive"))
      (node (ref "C36") (pin "2") (pintype "passive"))
      (node (ref "C37") (pin "2") (pintype "passive"))
      (node (ref "C4") (pin "1") (pintype "passive"))
      (node (ref "C5") (pin "1") (pintype "passive"))
      (node (ref "C6") (pin "1") (pintype "passive"))
      (node (ref "C7") (pin "1") (pintype "passive"))
      (node (ref "C8") (pin "1") (pintype "passive"))
      (node (ref "C9") (pin "1") (pintype "passive"))
      (node (ref "IC1") (pin "4") (pinfunction "GND_4") (pintype "passive"))
      (node (ref "IC2") (pin "12") (pinfunction "VSSQ_12") (pintype "passive"))
      (node (ref "IC2") (pin "28") (pinfunction "GND_28") (pintype "passive"))
      (node (ref "IC2") (pin "41") (pinfunction "GND_41") (pintype "passive"))
      (node (ref "IC2") (pin "46") (pinfunction "VSSQ_46") (pintype "passive"))
      (node (ref "IC2") (pin "52") (pinfunction "VSSQ_52") (pintype "passive"))
      (node (ref "IC2") (pin "54") (pinfunction "GND_54") (pintype "passive"))
      (node (ref "IC2") (pin "6") (pinfunction "VSSQ_6") (pintype "passive"))
      (node (ref "IC3") (pin "2") (pinfunction "GND_2") (pintype "passive"))
      (node (ref "MC1") (pin "102") (pinfunction "VSS_6_102") (pintype "passive"))
      (node (ref "MC1") (pin "113") (pinfunction "VSS_7_113") (pintype "passive"))
      (node (ref "MC1") (pin "126") (pinfunction "VSS_8_126") (pintype "passive"))
      (node (ref "MC1") (pin "135") (pinfunction "VSS_9_135") (pintype "passive"))
      (node (ref "MC1") (pin "14") (pinfunction "VSS_1_14") (pintype "passive"))
      (node (ref "MC1") (pin "148") (pinfunction "VSS_10_148") (pintype "passive"))
      (node (ref "MC1") (pin "158") (pinfunction "VSS_11_158") (pintype "passive"))
      (node (ref "MC1") (pin "22") (pinfunction "VSS_2_22") (pintype "passive"))
      (node (ref "MC1") (pin "37") (pinfunction "VSSA_37") (pintype "passive"))
      (node (ref "MC1") (pin "61") (pinfunction "VSS_3_61") (pintype "passive"))
      (node (ref "MC1") (pin "71") (pinfunction "VSS_4_71") (pintype "passive"))
      (node (ref "MC1") (pin "90") (pinfunction "VSS_5_90") (pintype "passive"))
      (node (ref "R14") (pin "1") (pintype "passive"))
      (node (ref "R16") (pin "1") (pintype "passive"))
      (node (ref "R17") (pin "1") (pintype "passive"))
      (node (ref "R20") (pin "1") (pintype "passive"))
      (node (ref "ST2") (pin "3") (pinfunction "GND_3") (pintype "passive"))
      (node (ref "ST3") (pin "29") (pinfunction "29_29") (pintype "passive"))
      (node (ref "ST3") (pin "3") (pinfunction "3_3") (pintype "passive"))
      (node (ref "ST3") (pin "35") (pinfunction "35_35") (pintype "passive"))
      (node (ref "ST3") (pin "36") (pinfunction "36_36") (pintype "passive"))
      (node (ref "ST4") (pin "6") (pinfunction "6_6") (pintype "passive"))
    )
    (net (code "82") (name "Net-(BATT1-+)") (class "Default")
      (node (ref "BATT1") (pin "2") (pinfunction "+_2") (pintype "passive"))
      (node (ref "D2") (pin "A") (pinfunction "A_A") (pintype "passive"))
    )
    (net (code "83") (name "Net-(D5-A)") (class "Default")
      (node (ref "D5") (pin "1") (pinfunction "A_1") (pintype "passive"))
      (node (ref "IC3") (pin "1") (pinfunction "SW_1") (pintype "passive"))
      (node (ref "L1") (pin "2") (pintype "passive"))
    )
    (net (code "84") (name "Net-(D5-K)") (class "Default")
      (node (ref "C29") (pin "2") (pintype "passive"))
      (node (ref "D5") (pin "2") (pinfunction "K_2") (pintype "passive"))
      (node (ref "ST3") (pin "2") (pinfunction "2_2") (pintype "passive"))
    )
    (net (code "85") (name "Net-(IC3-FB)") (class "Default")
      (node (ref "IC3") (pin "3") (pinfunction "FB_3") (pintype "passive"))
      (node (ref "R16") (pin "2") (pintype "passive"))
      (node (ref "ST3") (pin "1") (pinfunction "1_1") (pintype "passive"))
    )
    (net (code "86") (name "Net-(MC1-BOOT0)") (class "Default")
      (node (ref "MC1") (pin "166") (pinfunction "BOOT0_166") (pintype "passive"))
      (node (ref "R17") (pin "2") (pintype "passive"))
      (node (ref "S1") (pin "3") (pintype "passive"))
    )
    (net (code "87") (name "Net-(MC1-BYPASS_REG)") (class "Default")
      (node (ref "MC1") (pin "48") (pinfunction "BYPASS_REG_48") (pintype "passive"))
      (node (ref "R20") (pin "2") (pintype "passive"))
    )
    (net (code "88") (name "Net-(MC1-PA13_(JTMS{slash}SWDIO))") (class "Default")
      (node (ref "MC1") (pin "124") (pinfunction "PA13_(JTMS/SWDIO)_124") (pintype "passive"))
      (node (ref "R13") (pin "1") (pintype "passive"))
      (node (ref "ST2") (pin "2") (pinfunction "SWDIO/TMS_2") (pintype "passive"))
    )
    (net (code "89") (name "Net-(MC1-PA14_(JTCK{slash}SWCLK))") (class "Default")
      (node (ref "MC1") (pin "137") (pinfunction "PA14_(JTCK/SWCLK)_137") (pintype "passive"))
      (node (ref "R14") (pin "2") (pintype "passive"))
      (node (ref "ST2") (pin "4") (pinfunction "SWCLK/TCK_4") (pintype "passive"))
    )
    (net (code "90") (name "Net-(MC1-PA15_(JTDI))") (class "Default")
      (node (ref "MC1") (pin "138") (pinfunction "PA15_(JTDI)_138") (pintype "passive"))
      (node (ref "R12") (pin "1") (pintype "passive"))
      (node (ref "ST2") (pin "8") (pinfunction "TDI_8") (pintype "passive"))
    )
    (net (code "91") (name "Net-(MC1-PB2)") (class "Default")
      (node (ref "MC1") (pin "58") (pinfunction "PB2_58") (pintype "passive"))
      (node (ref "R3") (pin "2") (pintype "passive"))
    )
    (net (code "92") (name "Net-(MC1-PB3_(JTDO{slash}TRACESWO))") (class "Default")
      (node (ref "MC1") (pin "161") (pinfunction "PB3_(JTDO/TRACESWO)_161") (pintype "passive"))
      (node (ref "R10") (pin "1") (pintype "passive"))
      (node (ref "ST2") (pin "6") (pinfunction "SWO/TDO_6") (pintype "passive"))
    )
    (net (code "93") (name "Net-(MC1-PB4_(NJTRST))") (class "Default")
      (node (ref "MC1") (pin "162") (pinfunction "PB4_(NJTRST)_162") (pintype "passive"))
      (node (ref "R11") (pin "1") (pintype "passive"))
      (node (ref "ST2") (pin "9") (pinfunction "TRST_9") (pintype "passive"))
    )
    (net (code "94") (name "Net-(MC1-PC14_(OSC32_IN))") (class "Default")
      (node (ref "C36") (pin "1") (pintype "passive"))
      (node (ref "MC1") (pin "9") (pinfunction "PC14_(OSC32_IN)_9") (pintype "passive"))
      (node (ref "Q3") (pin "2") (pintype "passive"))
    )
    (net (code "95") (name "Net-(MC1-PC15_(OSC32_OUT))") (class "Default")
      (node (ref "C37") (pin "1") (pintype "passive"))
      (node (ref "MC1") (pin "10") (pinfunction "PC15_(OSC32_OUT)_10") (pintype "passive"))
      (node (ref "Q3") (pin "1") (pintype "passive"))
    )
    (net (code "96") (name "Net-(MC1-PDR_ON)") (class "Default")
      (node (ref "MC1") (pin "171") (pinfunction "PDR_ON_171") (pintype "passive"))
      (node (ref "R1") (pin "1") (pintype "passive"))
    )
    (net (code "97") (name "Net-(MC1-PH0_(OSC_IN))") (class "Default")
      (node (ref "C27") (pin "2") (pintype "passive"))
      (node (ref "MC1") (pin "29") (pinfunction "PH0_(OSC_IN)_29") (pintype "passive"))
      (node (ref "Q2") (pin "2") (pintype "passive"))
    )
    (net (code "98") (name "Net-(MC1-PH1_(OSC_OUT))") (class "Default")
      (node (ref "C28") (pin "2") (pintype "passive"))
      (node (ref "MC1") (pin "30") (pinfunction "PH1_(OSC_OUT)_30") (pintype "passive"))
      (node (ref "Q2") (pin "1") (pintype "passive"))
    )
    (net (code "99") (name "Net-(MC1-VBAT)") (class "Default")
      (node (ref "D1") (pin "K") (pinfunction "K_K") (pintype "passive"))
      (node (ref "D2") (pin "K") (pinfunction "K_K") (pintype "passive"))
      (node (ref "MC1") (pin "6") (pinfunction "VBAT_6") (pintype "passive"))
    )
    (net (code "100") (name "Net-(MC1-VCAP1)") (class "Default")
      (node (ref "C33") (pin "1") (pintype "passive"))
      (node (ref "MC1") (pin "81") (pinfunction "VCAP1_81") (pintype "passive"))
    )
    (net (code "101") (name "Net-(MC1-VCAP2)") (class "Default")
      (node (ref "C34") (pin "1") (pintype "passive"))
      (node (ref "MC1") (pin "125") (pinfunction "VCAP2_125") (pintype "passive"))
    )
    (net (code "102") (name "Net-(R18-Pad1)") (class "Default")
      (node (ref "R18") (pin "1") (pintype "passive"))
      (node (ref "R19") (pin "2") (pintype "passive"))
    )
    (net (code "103") (name "Net-(R19-Pad1)") (class "Default")
      (node (ref "R19") (pin "1") (pintype "passive"))
      (node (ref "R21") (pin "2") (pintype "passive"))
      (node (ref "ST4") (pin "4") (pinfunction "4_4") (pintype "passive"))
    )
    (net (code "104") (name "VCC") (class "Default")
      (node (ref "C1") (pin "2") (pintype "passive"))
      (node (ref "C10") (pin "1") (pintype "passive"))
      (node (ref "C11") (pin "2") (pintype "passive"))
      (node (ref "C12") (pin "1") (pintype "passive"))
      (node (ref "C13") (pin "2") (pintype "passive"))
      (node (ref "C14") (pin "2") (pintype "passive"))
      (node (ref "C15") (pin "2") (pintype "passive"))
      (node (ref "C16") (pin "2") (pintype "passive"))
      (node (ref "C17") (pin "2") (pintype "passive"))
      (node (ref "C18") (pin "2") (pintype "passive"))
      (node (ref "C19") (pin "2") (pintype "passive"))
      (node (ref "C2") (pin "2") (pintype "passive"))
      (node (ref "C20") (pin "2") (pintype "passive"))
      (node (ref "C21") (pin "2") (pintype "passive"))
      (node (ref "C22") (pin "2") (pintype "passive"))
      (node (ref "C23") (pin "2") (pintype "passive"))
      (node (ref "C24") (pin "2") (pintype "passive"))
      (node (ref "C25") (pin "2") (pintype "passive"))
      (node (ref "C26") (pin "2") (pintype "passive"))
      (node (ref "C3") (pin "2") (pintype "passive"))
      (node (ref "C4") (pin "2") (pintype "passive"))
      (node (ref "C5") (pin "2") (pintype "passive"))
      (node (ref "C6") (pin "2") (pintype "passive"))
      (node (ref "C7") (pin "2") (pintype "passive"))
      (node (ref "C8") (pin "2") (pintype "passive"))
      (node (ref "C9") (pin "2") (pintype "passive"))
      (node (ref "D1") (pin "A") (pinfunction "A_A") (pintype "passive"))
      (node (ref "IC1") (pin "8") (pinfunction "VCC_8") (pintype "passive"))
      (node (ref "IC2") (pin "1") (pinfunction "VCC_1") (pintype "passive"))
      (node (ref "IC2") (pin "14") (pinfunction "VCC_14") (pintype "passive"))
      (node (ref "IC2") (pin "27") (pinfunction "VCC_27") (pintype "passive"))
      (node (ref "IC2") (pin "3") (pinfunction "VDDQ_3") (pintype "passive"))
      (node (ref "IC2") (pin "43") (pinfunction "VDDQ_43") (pintype "passive"))
      (node (ref "IC2") (pin "49") (pinfunction "VDDQ_49") (pintype "passive"))
      (node (ref "IC2") (pin "9") (pinfunction "VDDQ_9") (pintype "passive"))
      (node (ref "MC1") (pin "103") (pinfunction "VDD_6_103") (pintype "passive"))
      (node (ref "MC1") (pin "114") (pinfunction "VDD_USB_114") (pintype "passive"))
      (node (ref "MC1") (pin "127") (pinfunction "VDD_5_127") (pintype "passive"))
      (node (ref "MC1") (pin "136") (pinfunction "VDD_4_136") (pintype "passive"))
      (node (ref "MC1") (pin "149") (pinfunction "VDD_3_149") (pintype "passive"))
      (node (ref "MC1") (pin "15") (pinfunction "VDD_14_15") (pintype "passive"))
      (node (ref "MC1") (pin "159") (pinfunction "VDD_2_159") (pintype "passive"))
      (node (ref "MC1") (pin "172") (pinfunction "VDD_1_172") (pintype "passive"))
      (node (ref "MC1") (pin "23") (pinfunction "VDD_13_23") (pintype "passive"))
      (node (ref "MC1") (pin "36") (pinfunction "VDD_12_36") (pintype "passive"))
      (node (ref "MC1") (pin "38") (pinfunction "VREF+_38") (pintype "passive"))
      (node (ref "MC1") (pin "39") (pinfunction "VDDA_39") (pintype "passive"))
      (node (ref "MC1") (pin "49") (pinfunction "VDD_11_49") (pintype "passive"))
      (node (ref "MC1") (pin "62") (pinfunction "VDD_10_62") (pintype "passive"))
      (node (ref "MC1") (pin "72") (pinfunction "VDD_9_72") (pintype "passive"))
      (node (ref "MC1") (pin "82") (pinfunction "VDD_8_82") (pintype "passive"))
      (node (ref "MC1") (pin "91") (pinfunction "VDD_7_91") (pintype "passive"))
      (node (ref "R1") (pin "2") (pintype "passive"))
      (node (ref "R10") (pin "2") (pintype "passive"))
      (node (ref "R11") (pin "2") (pintype "passive"))
      (node (ref "R12") (pin "2") (pintype "passive"))
      (node (ref "R13") (pin "2") (pintype "passive"))
      (node (ref "R15") (pin "2") (pintype "passive"))
      (node (ref "R18") (pin "2") (pintype "passive"))
      (node (ref "R2") (pin "2") (pintype "passive"))
      (node (ref "R8") (pin "2") (pintype "passive"))
      (node (ref "R9") (pin "2") (pintype "passive"))
      (node (ref "S1") (pin "1") (pintype "passive"))
      (node (ref "ST2") (pin "1") (pinfunction "VTRef_1") (pintype "passive"))
    )
    (net (code "105") (name "VCC2") (class "Default")
      (node (ref "C30") (pin "2") (pinfunction "A_2") (pintype "passive"))
      (node (ref "C31") (pin "2") (pintype "passive"))
      (node (ref "C32") (pin "2") (pintype "passive"))
      (node (ref "IC3") (pin "5") (pinfunction "VIN_5") (pintype "passive"))
      (node (ref "L1") (pin "1") (pintype "passive"))
      (node (ref "ST3") (pin "4") (pinfunction "4_4") (pintype "passive"))
      (node (ref "ST4") (pin "3") (pinfunction "3_3") (pintype "passive"))
    )
    (net (code "106") (name "unconnected-(IC2-NC-Pad36)") (class "Default")
      (node (ref "IC2") (pin "36") (pinfunction "NC_36") (pintype "passive"))
    )
    (net (code "107") (name "unconnected-(IC2-NC{slash}RFU-Pad40)") (class "Default")
      (node (ref "IC2") (pin "40") (pinfunction "NC/RFU_40") (pintype "passive"))
    )
    (net (code "108") (name "unconnected-(MC1-NC-Pad73)") (class "Default")
      (node (ref "MC1") (pin "73") (pinfunction "NC_73") (pintype "passive"))
    )
    (net (code "109") (name "unconnected-(MC1-PA0_(WKUP)-Pad40)") (class "Default")
      (node (ref "MC1") (pin "40") (pinfunction "PA0_(WKUP)_40") (pintype "passive"))
    )
    (net (code "110") (name "unconnected-(MC1-PA4-Pad50)") (class "Default")
      (node (ref "MC1") (pin "50") (pinfunction "PA4_50") (pintype "passive"))
    )
    (net (code "111") (name "unconnected-(MC1-PA8-Pad119)") (class "Default")
      (node (ref "MC1") (pin "119") (pinfunction "PA8_119") (pintype "passive"))
    )
    (net (code "112") (name "unconnected-(MC1-PA11-Pad122)") (class "Default")
      (node (ref "MC1") (pin "122") (pinfunction "PA11_122") (pintype "passive"))
    )
    (net (code "113") (name "unconnected-(MC1-PA12-Pad123)") (class "Default")
      (node (ref "MC1") (pin "123") (pinfunction "PA12_123") (pintype "passive"))
    )
    (net (code "114") (name "unconnected-(MC1-PB5-Pad163)") (class "Default")
      (node (ref "MC1") (pin "163") (pinfunction "PB5_163") (pintype "passive"))
    )
    (net (code "115") (name "unconnected-(MC1-PB7-Pad165)") (class "Default")
      (node (ref "MC1") (pin "165") (pinfunction "PB7_165") (pintype "passive"))
    )
    (net (code "116") (name "unconnected-(MC1-PB8-Pad167)") (class "Default")
      (node (ref "MC1") (pin "167") (pinfunction "PB8_167") (pintype "passive"))
    )
    (net (code "117") (name "unconnected-(MC1-PB12-Pad92)") (class "Default")
      (node (ref "MC1") (pin "92") (pinfunction "PB12_92") (pintype "passive"))
    )
    (net (code "118") (name "unconnected-(MC1-PB13-Pad93)") (class "Default")
      (node (ref "MC1") (pin "93") (pinfunction "PB13_93") (pintype "passive"))
    )
    (net (code "119") (name "unconnected-(MC1-PB14-Pad94)") (class "Default")
      (node (ref "MC1") (pin "94") (pinfunction "PB14_94") (pintype "passive"))
    )
    (net (code "120") (name "unconnected-(MC1-PB15-Pad95)") (class "Default")
      (node (ref "MC1") (pin "95") (pinfunction "PB15_95") (pintype "passive"))
    )
    (net (code "121") (name "unconnected-(MC1-PC1-Pad33)") (class "Default")
      (node (ref "MC1") (pin "33") (pinfunction "PC1_33") (pintype "passive"))
    )
    (net (code "122") (name "unconnected-(MC1-PC4-Pad54)") (class "Default")
      (node (ref "MC1") (pin "54") (pinfunction "PC4_54") (pintype "passive"))
    )
    (net (code "123") (name "unconnected-(MC1-PC5-Pad55)") (class "Default")
      (node (ref "MC1") (pin "55") (pinfunction "PC5_55") (pintype "passive"))
    )
    (net (code "124") (name "unconnected-(MC1-PC6-Pad115)") (class "Default")
      (node (ref "MC1") (pin "115") (pinfunction "PC6_115") (pintype "passive"))
    )
    (net (code "125") (name "unconnected-(MC1-PC7-Pad116)") (class "Default")
      (node (ref "MC1") (pin "116") (pinfunction "PC7_116") (pintype "passive"))
    )
    (net (code "126") (name "unconnected-(MC1-PC8-Pad117)") (class "Default")
      (node (ref "MC1") (pin "117") (pinfunction "PC8_117") (pintype "passive"))
    )
    (net (code "127") (name "unconnected-(MC1-PC9-Pad118)") (class "Default")
      (node (ref "MC1") (pin "118") (pinfunction "PC9_118") (pintype "passive"))
    )
    (net (code "128") (name "unconnected-(MC1-PC10-Pad139)") (class "Default")
      (node (ref "MC1") (pin "139") (pinfunction "PC10_139") (pintype "passive"))
    )
    (net (code "129") (name "unconnected-(MC1-PC11-Pad140)") (class "Default")
      (node (ref "MC1") (pin "140") (pinfunction "PC11_140") (pintype "passive"))
    )
    (net (code "130") (name "unconnected-(MC1-PC12-Pad141)") (class "Default")
      (node (ref "MC1") (pin "141") (pinfunction "PC12_141") (pintype "passive"))
    )
    (net (code "131") (name "unconnected-(MC1-PC13-Pad8)") (class "Default")
      (node (ref "MC1") (pin "8") (pinfunction "PC13_8") (pintype "passive"))
    )
    (net (code "132") (name "unconnected-(MC1-PD2-Pad144)") (class "Default")
      (node (ref "MC1") (pin "144") (pinfunction "PD2_144") (pintype "passive"))
    )
    (net (code "133") (name "unconnected-(MC1-PD5-Pad147)") (class "Default")
      (node (ref "MC1") (pin "147") (pinfunction "PD5_147") (pintype "passive"))
    )
    (net (code "134") (name "unconnected-(MC1-PD7-Pad151)") (class "Default")
      (node (ref "MC1") (pin "151") (pinfunction "PD7_151") (pintype "passive"))
    )
    (net (code "135") (name "unconnected-(MC1-PD11-Pad99)") (class "Default")
      (node (ref "MC1") (pin "99") (pinfunction "PD11_99") (pintype "passive"))
    )
    (net (code "136") (name "unconnected-(MC1-PD12-Pad100)") (class "Default")
      (node (ref "MC1") (pin "100") (pinfunction "PD12_100") (pintype "passive"))
    )
    (net (code "137") (name "unconnected-(MC1-PD13-Pad101)") (class "Default")
      (node (ref "MC1") (pin "101") (pinfunction "PD13_101") (pintype "passive"))
    )
    (net (code "138") (name "unconnected-(MC1-PE3-Pad2)") (class "Default")
      (node (ref "MC1") (pin "2") (pinfunction "PE3_2") (pintype "passive"))
    )
    (net (code "139") (name "unconnected-(MC1-PF7-Pad25)") (class "Default")
      (node (ref "MC1") (pin "25") (pinfunction "PF7_25") (pintype "passive"))
    )
    (net (code "140") (name "unconnected-(MC1-PG2-Pad106)") (class "Default")
      (node (ref "MC1") (pin "106") (pinfunction "PG2_106") (pintype "passive"))
    )
    (net (code "141") (name "unconnected-(MC1-PG3-Pad107)") (class "Default")
      (node (ref "MC1") (pin "107") (pinfunction "PG3_107") (pintype "passive"))
    )
    (net (code "142") (name "unconnected-(MC1-PG9-Pad152)") (class "Default")
      (node (ref "MC1") (pin "152") (pinfunction "PG9_152") (pintype "passive"))
    )
    (net (code "143") (name "unconnected-(MC1-PG10-Pad153)") (class "Default")
      (node (ref "MC1") (pin "153") (pinfunction "PG10_153") (pintype "passive"))
    )
    (net (code "144") (name "unconnected-(MC1-PG13-Pad156)") (class "Default")
      (node (ref "MC1") (pin "156") (pinfunction "PG13_156") (pintype "passive"))
    )
    (net (code "145") (name "unconnected-(MC1-PG14-Pad157)") (class "Default")
      (node (ref "MC1") (pin "157") (pinfunction "PG14_157") (pintype "passive"))
    )
    (net (code "146") (name "unconnected-(MC1-PH3-Pad44)") (class "Default")
      (node (ref "MC1") (pin "44") (pinfunction "PH3_44") (pintype "passive"))
    )
    (net (code "147") (name "unconnected-(MC1-PH4-Pad45)") (class "Default")
      (node (ref "MC1") (pin "45") (pinfunction "PH4_45") (pintype "passive"))
    )
    (net (code "148") (name "unconnected-(MC1-PH6-Pad83)") (class "Default")
      (node (ref "MC1") (pin "83") (pinfunction "PH6_83") (pintype "passive"))
    )
    (net (code "149") (name "unconnected-(MC1-PH9-Pad86)") (class "Default")
      (node (ref "MC1") (pin "86") (pinfunction "PH9_86") (pintype "passive"))
    )
    (net (code "150") (name "unconnected-(MC1-PH10-Pad87)") (class "Default")
      (node (ref "MC1") (pin "87") (pinfunction "PH10_87") (pintype "passive"))
    )
    (net (code "151") (name "unconnected-(MC1-PH11-Pad88)") (class "Default")
      (node (ref "MC1") (pin "88") (pinfunction "PH11_88") (pintype "passive"))
    )
    (net (code "152") (name "unconnected-(MC1-PH12-Pad89)") (class "Default")
      (node (ref "MC1") (pin "89") (pinfunction "PH12_89") (pintype "passive"))
    )
    (net (code "153") (name "unconnected-(MC1-PH13-Pad128)") (class "Default")
      (node (ref "MC1") (pin "128") (pinfunction "PH13_128") (pintype "passive"))
    )
    (net (code "154") (name "unconnected-(MC1-PH15-Pad130)") (class "Default")
      (node (ref "MC1") (pin "130") (pinfunction "PH15_130") (pintype "passive"))
    )
    (net (code "155") (name "unconnected-(MC1-PI0-Pad131)") (class "Default")
      (node (ref "MC1") (pin "131") (pinfunction "PI0_131") (pintype "passive"))
    )
    (net (code "156") (name "unconnected-(MC1-PI3-Pad134)") (class "Default")
      (node (ref "MC1") (pin "134") (pinfunction "PI3_134") (pintype "passive"))
    )
    (net (code "157") (name "unconnected-(MC1-PI5-Pad174)") (class "Default")
      (node (ref "MC1") (pin "174") (pinfunction "PI5_174") (pintype "passive"))
    )
    (net (code "158") (name "unconnected-(MC1-PI7-Pad176)") (class "Default")
      (node (ref "MC1") (pin "176") (pinfunction "PI7_176") (pintype "passive"))
    )
    (net (code "159") (name "unconnected-(MC1-PI11-Pad13)") (class "Default")
      (node (ref "MC1") (pin "13") (pinfunction "PI11_13") (pintype "passive"))
    )
    (net (code "160") (name "unconnected-(ST2-+5V-Pad5)") (class "Default")
      (node (ref "ST2") (pin "5") (pinfunction "+5V_5") (pintype "passive"))
    )
    (net (code "161") (name "unconnected-(ST2-RTCK-Pad7)") (class "Default")
      (node (ref "ST2") (pin "7") (pinfunction "RTCK_7") (pintype "passive"))
    )
    (net (code "162") (name "unconnected-(ST3-Pad37)") (class "Default")
      (node (ref "ST3") (pin "37") (pinfunction "37_37") (pintype "passive"))
    )
    (net (code "163") (name "unconnected-(ST3-Pad38)") (class "Default")
      (node (ref "ST3") (pin "38") (pinfunction "38_38") (pintype "passive"))
    )
    (net (code "164") (name "unconnected-(ST3-Pad39)") (class "Default")
      (node (ref "ST3") (pin "39") (pinfunction "39_39") (pintype "passive"))
    )
    (net (code "165") (name "unconnected-(ST3-Pad40)") (class "Default")
      (node (ref "ST3") (pin "40") (pinfunction "40_40") (pintype "passive"))
    )
  )
)
